# jtag-buffer.net
KiCad netlist of a schematic drawn in Altium Designer
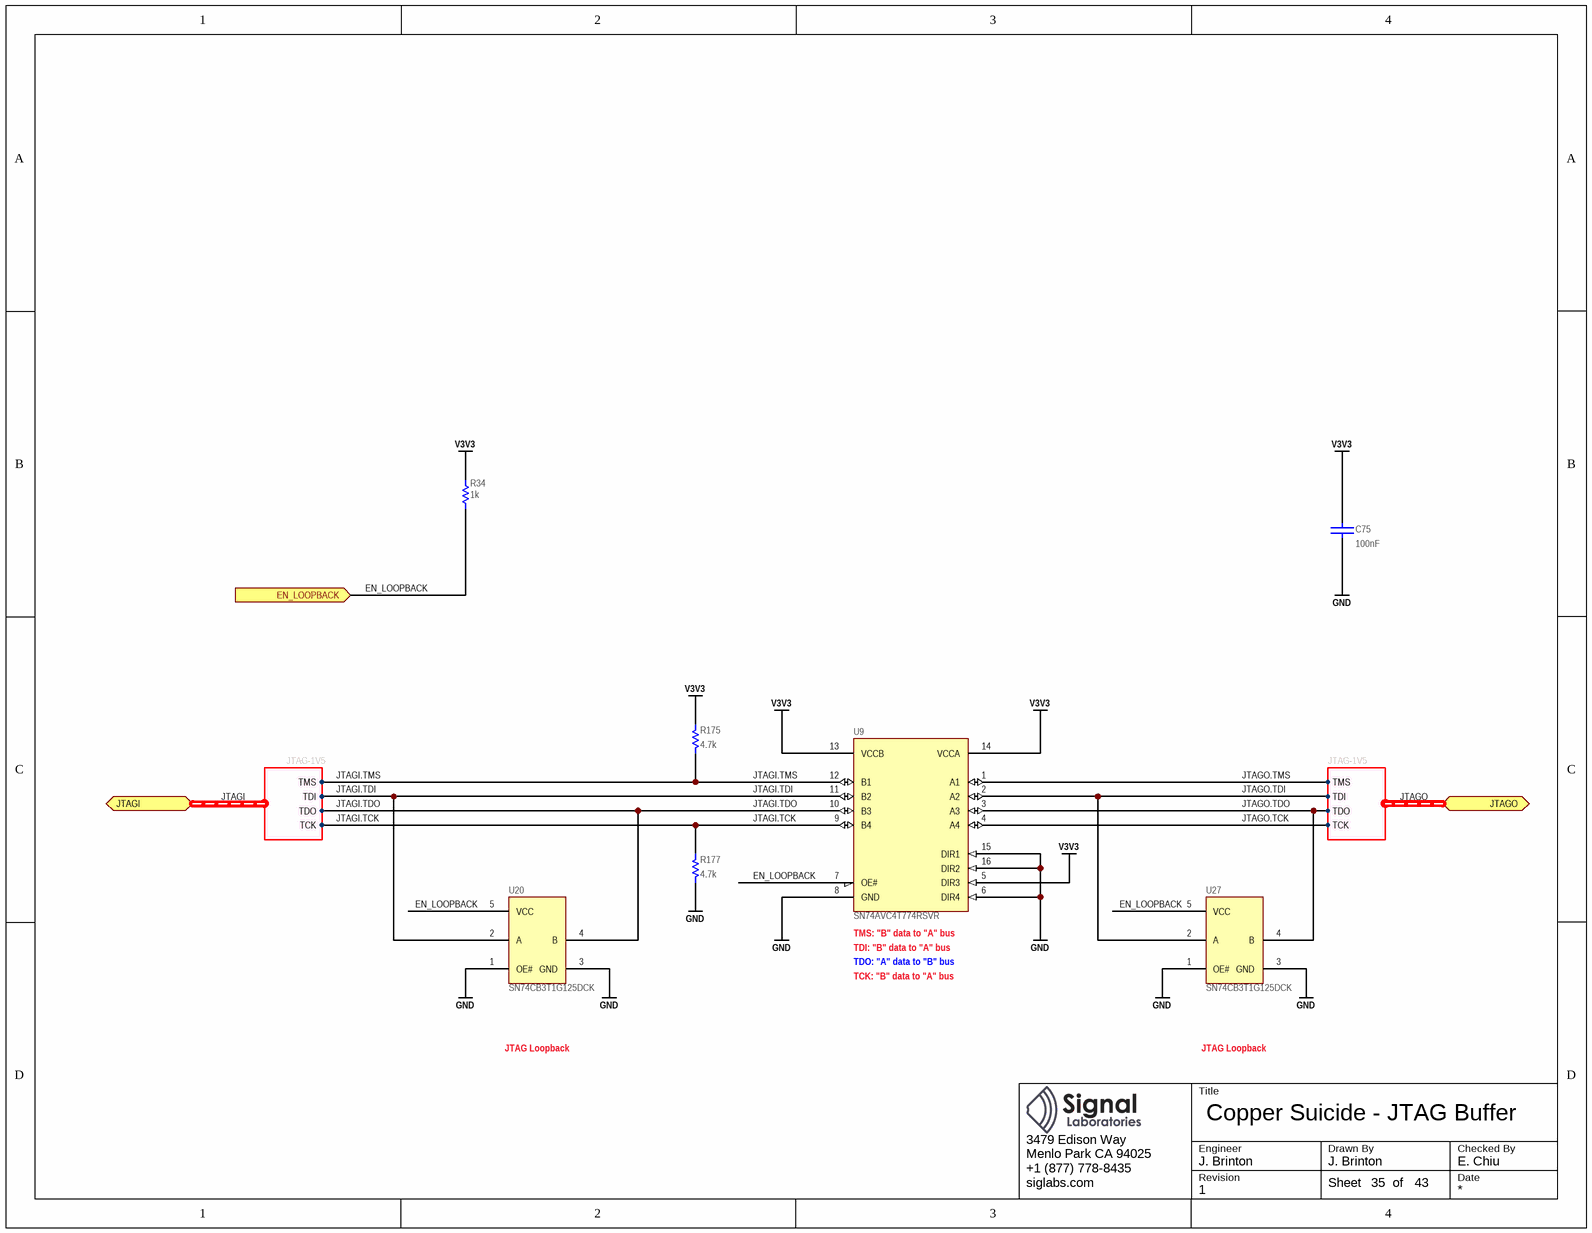
[diagram p0: jtag-buffer.SchDoc]

(export (version "E")
  (design (tool "Eeschema 10.0.6"))
  (components
    (comp (ref "C75")
      (value "100nF")
      (footprint "CAPC100X50X55L25N")
      (description "Ceramic Capacitor 100nF ±10% 50V X7R 0402")
      (fields (field (name "MANUFACTURER") "Murata") (field (name "TOLERANCE") "±10%"))
      (libsource (lib "generic") (part "CAP"))
    )
    (comp (ref "R34")
      (value "1k")
      (footprint "RESC1005X40N")
      (description "Thick Film Resistor 1k ±1% 0.1W 50V 0402")
      (fields (field (name "MANUFACTURER") "Panasonic") (field (name "TOLERANCE") "±1%"))
      (libsource (lib "generic") (part "RES"))
    )
    (comp (ref "R175")
      (value "4.7k")
      (footprint "RESC1005X40N")
      (description "Thick Film Resistor 4.7k ±1% 0.1W 75V 0402")
      (fields (field (name "TOLERANCE") "±1%") (field (name "MANUFACTURER") "Panasonic"))
      (libsource (lib "generic") (part "RES"))
    )
    (comp (ref "R177")
      (value "4.7k")
      (footprint "RESC1005X40N")
      (description "Thick Film Resistor 4.7k ±1% 0.1W 75V 0402")
      (fields (field (name "TOLERANCE") "±1%") (field (name "MANUFACTURER") "Panasonic"))
      (libsource (lib "generic") (part "RES"))
    )
    (comp (ref "U9")
      (value "SN74AVC4T774RSVR")
      (footprint "RSV")
      (description "4-Bit Dual-Supply Bus Transceiver")
      (fields (field (name "MANUFACTURER") "Texas Instruments"))
      (libsource (lib "ti") (part "SN74AVC4T774RSVR"))
    )
    (comp (ref "U20")
      (value "SN74CB3T1G125DCK")
      (footprint "texas_instruments:DCK")
      (description "Single FET Bus Switch")
      (fields (field (name "MANUFACTURER") "Texas Instruments"))
      (libsource (lib "ti") (part "SN74CB3T1G125DCK"))
    )
    (comp (ref "U27")
      (value "SN74CB3T1G125DCK")
      (footprint "texas_instruments:DCK")
      (description "Single FET Bus Switch")
      (fields (field (name "MANUFACTURER") "Texas Instruments"))
      (libsource (lib "ti") (part "SN74CB3T1G125DCK"))
    )
  )
  (nets
    (net (code "3") (name "/EN_LOOPBACK") (class "Default")
      (node (ref "R34") (pin "1") (pinfunction "1_1") (pintype "passive"))
      (node (ref "U20") (pin "5") (pinfunction "VCC_5") (pintype "passive"))
      (node (ref "U27") (pin "5") (pinfunction "VCC_5") (pintype "passive"))
      (node (ref "U9") (pin "7") (pinfunction "OE#_7") (pintype "passive"))
    )
    (net (code "4") (name "/JTAGI.TCK") (class "Default")
      (node (ref "R177") (pin "2") (pinfunction "2_2") (pintype "passive"))
      (node (ref "U9") (pin "9") (pinfunction "B4_9") (pintype "bidirectional"))
    )
    (net (code "5") (name "/JTAGI.TDI") (class "Default")
      (node (ref "U20") (pin "2") (pinfunction "A_2") (pintype "passive"))
      (node (ref "U9") (pin "11") (pinfunction "B2_11") (pintype "bidirectional"))
    )
    (net (code "6") (name "/JTAGI.TDO") (class "Default")
      (node (ref "U20") (pin "4") (pinfunction "B_4") (pintype "passive"))
      (node (ref "U9") (pin "10") (pinfunction "B3_10") (pintype "bidirectional"))
    )
    (net (code "7") (name "/JTAGI.TMS") (class "Default")
      (node (ref "R175") (pin "1") (pinfunction "1_1") (pintype "passive"))
      (node (ref "U9") (pin "12") (pinfunction "B1_12") (pintype "bidirectional"))
    )
    (net (code "9") (name "/JTAGO.TCK") (class "Default")
      (node (ref "U9") (pin "4") (pinfunction "A4_4") (pintype "bidirectional"))
    )
    (net (code "10") (name "/JTAGO.TDI") (class "Default")
      (node (ref "U27") (pin "2") (pinfunction "A_2") (pintype "passive"))
      (node (ref "U9") (pin "2") (pinfunction "A2_2") (pintype "bidirectional"))
    )
    (net (code "11") (name "/JTAGO.TDO") (class "Default")
      (node (ref "U27") (pin "4") (pinfunction "B_4") (pintype "passive"))
      (node (ref "U9") (pin "3") (pinfunction "A3_3") (pintype "bidirectional"))
    )
    (net (code "12") (name "/JTAGO.TMS") (class "Default")
      (node (ref "U9") (pin "1") (pinfunction "A1_1") (pintype "bidirectional"))
    )
    (net (code "14") (name "GND") (class "Default")
      (node (ref "C75") (pin "1") (pinfunction "1_1") (pintype "passive"))
      (node (ref "R177") (pin "1") (pinfunction "1_1") (pintype "passive"))
      (node (ref "U20") (pin "1") (pinfunction "OE#_1") (pintype "passive"))
      (node (ref "U20") (pin "3") (pinfunction "GND_3") (pintype "passive"))
      (node (ref "U27") (pin "1") (pinfunction "OE#_1") (pintype "passive"))
      (node (ref "U27") (pin "3") (pinfunction "GND_3") (pintype "passive"))
      (node (ref "U9") (pin "15") (pinfunction "DIR1_15") (pintype "input"))
      (node (ref "U9") (pin "16") (pinfunction "DIR2_16") (pintype "input"))
      (node (ref "U9") (pin "6") (pinfunction "DIR4_6") (pintype "input"))
      (node (ref "U9") (pin "8") (pinfunction "GND_8") (pintype "power_in"))
    )
    (net (code "15") (name "V3V3") (class "Default")
      (node (ref "C75") (pin "2") (pinfunction "2_2") (pintype "passive"))
      (node (ref "R175") (pin "2") (pinfunction "2_2") (pintype "passive"))
      (node (ref "R34") (pin "2") (pinfunction "2_2") (pintype "passive"))
      (node (ref "U9") (pin "13") (pinfunction "VCCB_13") (pintype "power_in"))
      (node (ref "U9") (pin "14") (pinfunction "VCCA_14") (pintype "power_in"))
      (node (ref "U9") (pin "5") (pinfunction "DIR3_5") (pintype "input"))
    )
  )
)
